# wcdl.net
KiCad netlist of a schematic drawn in EAGLE
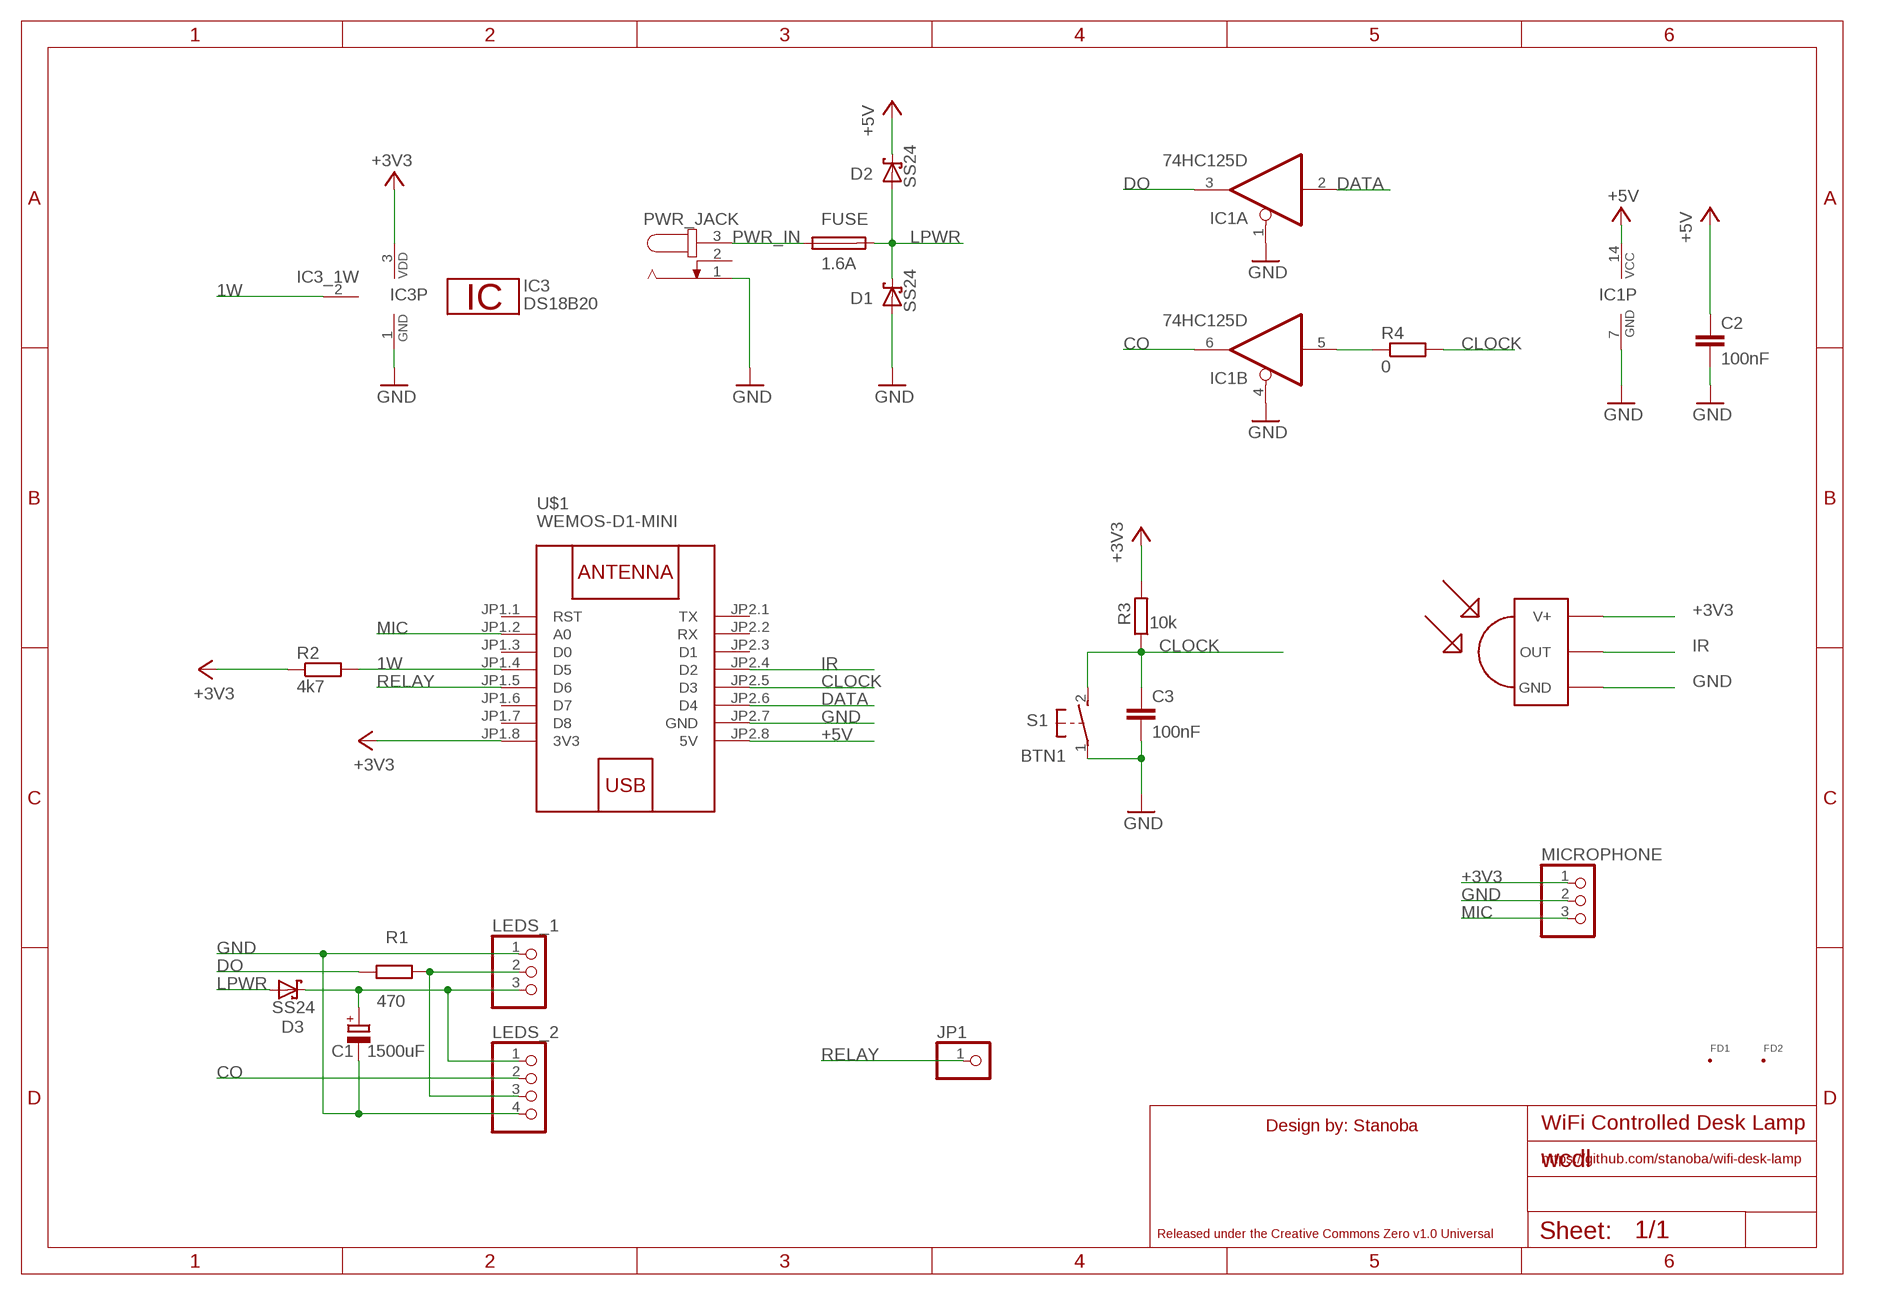
[diagram p0: schematic, sheet 1]

(export (version "E")
  (design (tool "Eeschema 10.0.6"))
  (components
    (comp (ref "C1")
      (value "1500uF")
      (footprint "eagle-import:PANASONIC_G")
      (libsource (lib "eagle-import") (part "CPOL-EUG"))
    )
    (comp (ref "C2")
      (value "100nF")
      (footprint "eagle-import:C0603")
      (libsource (lib "eagle-import") (part "C-EUC0603"))
    )
    (comp (ref "C3")
      (value "100nF")
      (footprint "eagle-import:C0603")
      (libsource (lib "eagle-import") (part "C-EUC0603"))
    )
    (comp (ref "D1")
      (value "SS24")
      (footprint "eagle-import:SMB")
      (libsource (lib "eagle-import") (part "SCHOTTKY-DIODESMD"))
    )
    (comp (ref "D2")
      (value "SS24")
      (footprint "eagle-import:SMB")
      (libsource (lib "eagle-import") (part "SCHOTTKY-DIODESMD"))
    )
    (comp (ref "D3")
      (value "SS24")
      (footprint "eagle-import:SMB")
      (libsource (lib "eagle-import") (part "SCHOTTKY-DIODESMD"))
    )
    (comp (ref "FD1")
      (value "FID_40MIL")
      (footprint "eagle-import:FID_040")
      (libsource (lib "eagle-import") (part "FID_40MIL"))
    )
    (comp (ref "FD2")
      (value "FID_40MIL")
      (footprint "eagle-import:FID_040")
      (libsource (lib "eagle-import") (part "FID_40MIL"))
    )
    (comp (ref "FUSE")
      (value "1.6A")
      (footprint "eagle-import:SHK20L")
      (libsource (lib "eagle-import") (part "FUSESHK20L"))
    )
    (comp (ref "IC1")
      (value "74HC125D")
      (footprint "eagle-import:SO14")
      (libsource (lib "eagle-import") (part "74125DHC"))
    )
    (comp (ref "IC3")
      (value "DS18B20")
      (footprint "eagle-import:TO92-")
      (libsource (lib "eagle-import") (part "DS18B20"))
    )
    (comp (ref "JP1")
      (value "PINHD-1X1")
      (footprint "eagle-import:1X01")
      (libsource (lib "eagle-import") (part "PINHD-1X1"))
    )
    (comp (ref "LEDS_1")
      (value "PINHD-1X3")
      (footprint "eagle-import:1X03")
      (libsource (lib "eagle-import") (part "PINHD-1X3"))
    )
    (comp (ref "LEDS_2")
      (value "PINHD-1X4")
      (footprint "eagle-import:1X04")
      (libsource (lib "eagle-import") (part "PINHD-1X4"))
    )
    (comp (ref "MICROPHONE")
      (value "PINHD-1X3")
      (footprint "eagle-import:1X03")
      (libsource (lib "eagle-import") (part "PINHD-1X3"))
    )
    (comp (ref "PWR_JACK")
      (value "JACK-PLUG0")
      (footprint "eagle-import:SPC4077")
      (libsource (lib "eagle-import") (part "JACK-PLUG0"))
    )
    (comp (ref "R1")
      (value "470")
      (footprint "eagle-import:R0603")
      (libsource (lib "eagle-import") (part "R-EU_R0603"))
    )
    (comp (ref "R2")
      (value "4k7")
      (footprint "eagle-import:R0603")
      (libsource (lib "eagle-import") (part "R-EU_R0603"))
    )
    (comp (ref "R3")
      (value "10k")
      (footprint "eagle-import:R0603")
      (libsource (lib "eagle-import") (part "R-EU_R0603"))
    )
    (comp (ref "R4")
      (value "0")
      (footprint "eagle-import:R0402")
      (libsource (lib "eagle-import") (part "R-EU_R0402"))
    )
    (comp (ref "S1")
      (value "BTN1")
      (footprint "eagle-import:B3F-31XX")
      (fields (field (name "MPN") "B3F-3100"))
      (libsource (lib "eagle-import") (part "31-XX"))
    )
    (comp (ref "U$1")
      (value "WEMOS-D1-MINI")
      (footprint "eagle-import:WEMOS-D1-MINI")
      (libsource (lib "eagle-import") (part "WEMOS-D1-MINI"))
    )
    (comp (ref "U$2")
      (value "TSOP1838")
      (footprint "eagle-import:TSOP18XX")
      (libsource (lib "eagle-import") (part "TSOP1838"))
    )
  )
  (nets
    (net (code "1") (name "+3V3") (class "Default")
      (node (ref "IC3") (pin "3") (pinfunction "VDD_3") (pintype "power_in"))
      (node (ref "MICROPHONE") (pin "1") (pinfunction "1_1") (pintype "passive"))
      (node (ref "R2") (pin "1") (pinfunction "1_1") (pintype "passive"))
      (node (ref "R3") (pin "2") (pinfunction "2_2") (pintype "passive"))
      (node (ref "U$1") (pin "JP1.8") (pinfunction "3V3_JP1.8") (pintype "power_in"))
      (node (ref "U$2") (pin "VCC") (pinfunction "V+_VCC") (pintype "bidirectional"))
    )
    (net (code "2") (name "+5V") (class "Default")
      (node (ref "C2") (pin "1") (pinfunction "1_1") (pintype "passive"))
      (node (ref "D2") (pin "C") (pinfunction "C_C") (pintype "passive"))
      (node (ref "IC1") (pin "14") (pinfunction "VCC_14") (pintype "power_in"))
      (node (ref "U$1") (pin "JP2.8") (pinfunction "5V_JP2.8") (pintype "power_in"))
    )
    (net (code "3") (name "/1W") (class "Default")
      (node (ref "IC3") (pin "2") (pinfunction "1W_2") (pintype "power_in"))
      (node (ref "R2") (pin "2") (pinfunction "2_2") (pintype "passive"))
      (node (ref "U$1") (pin "JP1.4") (pinfunction "D5_JP1.4") (pintype "bidirectional"))
    )
    (net (code "4") (name "/CLOCK") (class "Default")
      (node (ref "C3") (pin "1") (pinfunction "1_1") (pintype "passive"))
      (node (ref "R3") (pin "1") (pinfunction "1_1") (pintype "passive"))
      (node (ref "R4") (pin "2") (pinfunction "2_2") (pintype "passive"))
      (node (ref "S1") (pin "2") (pinfunction "S_2") (pintype "passive"))
      (node (ref "U$1") (pin "JP2.5") (pinfunction "D3_JP2.5") (pintype "bidirectional"))
    )
    (net (code "5") (name "/CO") (class "Default")
      (node (ref "IC1") (pin "6") (pinfunction "O_6") (pintype "tri_state"))
      (node (ref "LEDS_2") (pin "2") (pinfunction "2_2") (pintype "passive"))
    )
    (net (code "6") (name "/DATA") (class "Default")
      (node (ref "IC1") (pin "2") (pinfunction "I_2") (pintype "input"))
      (node (ref "U$1") (pin "JP2.6") (pinfunction "D4_JP2.6") (pintype "bidirectional"))
    )
    (net (code "7") (name "/DO") (class "Default")
      (node (ref "IC1") (pin "3") (pinfunction "O_3") (pintype "tri_state"))
      (node (ref "R1") (pin "1") (pinfunction "1_1") (pintype "passive"))
    )
    (net (code "8") (name "/IR") (class "Default")
      (node (ref "U$1") (pin "JP2.4") (pinfunction "D2_JP2.4") (pintype "bidirectional"))
      (node (ref "U$2") (pin "OUT") (pinfunction "OUT_OUT") (pintype "bidirectional"))
    )
    (net (code "9") (name "/LPWR") (class "Default")
      (node (ref "D1") (pin "C") (pinfunction "C_C") (pintype "passive"))
      (node (ref "D2") (pin "A") (pinfunction "A_A") (pintype "passive"))
      (node (ref "D3") (pin "A") (pinfunction "A_A") (pintype "passive"))
      (node (ref "FUSE") (pin "2A") (pinfunction "2_2A") (pintype "passive"))
    )
    (net (code "10") (name "/MIC") (class "Default")
      (node (ref "MICROPHONE") (pin "3") (pinfunction "3_3") (pintype "passive"))
      (node (ref "U$1") (pin "JP1.2") (pinfunction "A0_JP1.2") (pintype "bidirectional"))
    )
    (net (code "11") (name "/PWR_IN") (class "Default")
      (node (ref "FUSE") (pin "1A") (pinfunction "1_1A") (pintype "passive"))
      (node (ref "PWR_JACK") (pin "3") (pinfunction "3_3") (pintype "passive"))
    )
    (net (code "12") (name "/RELAY") (class "Default")
      (node (ref "JP1") (pin "1") (pinfunction "1_1") (pintype "passive"))
      (node (ref "U$1") (pin "JP1.5") (pinfunction "D6_JP1.5") (pintype "bidirectional"))
    )
    (net (code "13") (name "GND") (class "Default")
      (node (ref "C1") (pin "-") (pinfunction "-_-") (pintype "passive"))
      (node (ref "C2") (pin "2") (pinfunction "2_2") (pintype "passive"))
      (node (ref "C3") (pin "2") (pinfunction "2_2") (pintype "passive"))
      (node (ref "D1") (pin "A") (pinfunction "A_A") (pintype "passive"))
      (node (ref "IC1") (pin "1") (pinfunction "OE_1") (pintype "input"))
      (node (ref "IC1") (pin "4") (pinfunction "OE_4") (pintype "input"))
      (node (ref "IC1") (pin "7") (pinfunction "GND_7") (pintype "power_in"))
      (node (ref "IC3") (pin "1") (pinfunction "GND_1") (pintype "power_in"))
      (node (ref "LEDS_1") (pin "1") (pinfunction "1_1") (pintype "passive"))
      (node (ref "LEDS_2") (pin "4") (pinfunction "4_4") (pintype "passive"))
      (node (ref "MICROPHONE") (pin "2") (pinfunction "2_2") (pintype "passive"))
      (node (ref "PWR_JACK") (pin "1") (pinfunction "1_1") (pintype "passive"))
      (node (ref "S1") (pin "1") (pinfunction "P_1") (pintype "passive"))
      (node (ref "U$1") (pin "JP2.7") (pinfunction "GND_JP2.7") (pintype "power_in"))
      (node (ref "U$2") (pin "GND") (pinfunction "GND_GND") (pintype "bidirectional"))
    )
    (net (code "14") (name "Net-(C1-Pad+)") (class "Default")
      (node (ref "C1") (pin "+") (pinfunction "+_+") (pintype "passive"))
      (node (ref "D3") (pin "C") (pinfunction "C_C") (pintype "passive"))
      (node (ref "LEDS_1") (pin "3") (pinfunction "3_3") (pintype "passive"))
      (node (ref "LEDS_2") (pin "1") (pinfunction "1_1") (pintype "passive"))
    )
    (net (code "15") (name "Net-(IC1B-I)") (class "Default")
      (node (ref "IC1") (pin "5") (pinfunction "I_5") (pintype "input"))
      (node (ref "R4") (pin "1") (pinfunction "1_1") (pintype "passive"))
    )
    (net (code "16") (name "Net-(LEDS_1-Pad2)") (class "Default")
      (node (ref "LEDS_1") (pin "2") (pinfunction "2_2") (pintype "passive"))
      (node (ref "LEDS_2") (pin "3") (pinfunction "3_3") (pintype "passive"))
      (node (ref "R1") (pin "2") (pinfunction "2_2") (pintype "passive"))
    )
    (net (code "17") (name "unconnected-(PWR_JACK-Pad2)") (class "Default")
      (node (ref "PWR_JACK") (pin "2") (pinfunction "2_2") (pintype "passive"))
    )
    (net (code "18") (name "unconnected-(U$1-D0-PadJP1.3)") (class "Default")
      (node (ref "U$1") (pin "JP1.3") (pinfunction "D0_JP1.3") (pintype "bidirectional"))
    )
    (net (code "19") (name "unconnected-(U$1-D1-PadJP2.3)") (class "Default")
      (node (ref "U$1") (pin "JP2.3") (pinfunction "D1_JP2.3") (pintype "bidirectional"))
    )
    (net (code "20") (name "unconnected-(U$1-D7-PadJP1.6)") (class "Default")
      (node (ref "U$1") (pin "JP1.6") (pinfunction "D7_JP1.6") (pintype "bidirectional"))
    )
    (net (code "21") (name "unconnected-(U$1-D8-PadJP1.7)") (class "Default")
      (node (ref "U$1") (pin "JP1.7") (pinfunction "D8_JP1.7") (pintype "bidirectional"))
    )
    (net (code "22") (name "unconnected-(U$1-RST-PadJP1.1)") (class "Default")
      (node (ref "U$1") (pin "JP1.1") (pinfunction "RST_JP1.1") (pintype "bidirectional"))
    )
    (net (code "23") (name "unconnected-(U$1-RX-PadJP2.2)") (class "Default")
      (node (ref "U$1") (pin "JP2.2") (pinfunction "RX_JP2.2") (pintype "bidirectional"))
    )
    (net (code "24") (name "unconnected-(U$1-TX-PadJP2.1)") (class "Default")
      (node (ref "U$1") (pin "JP2.1") (pinfunction "TX_JP2.1") (pintype "bidirectional"))
    )
  )
)
